# CorruptCore.net
KiCad netlist of a schematic drawn in EAGLE
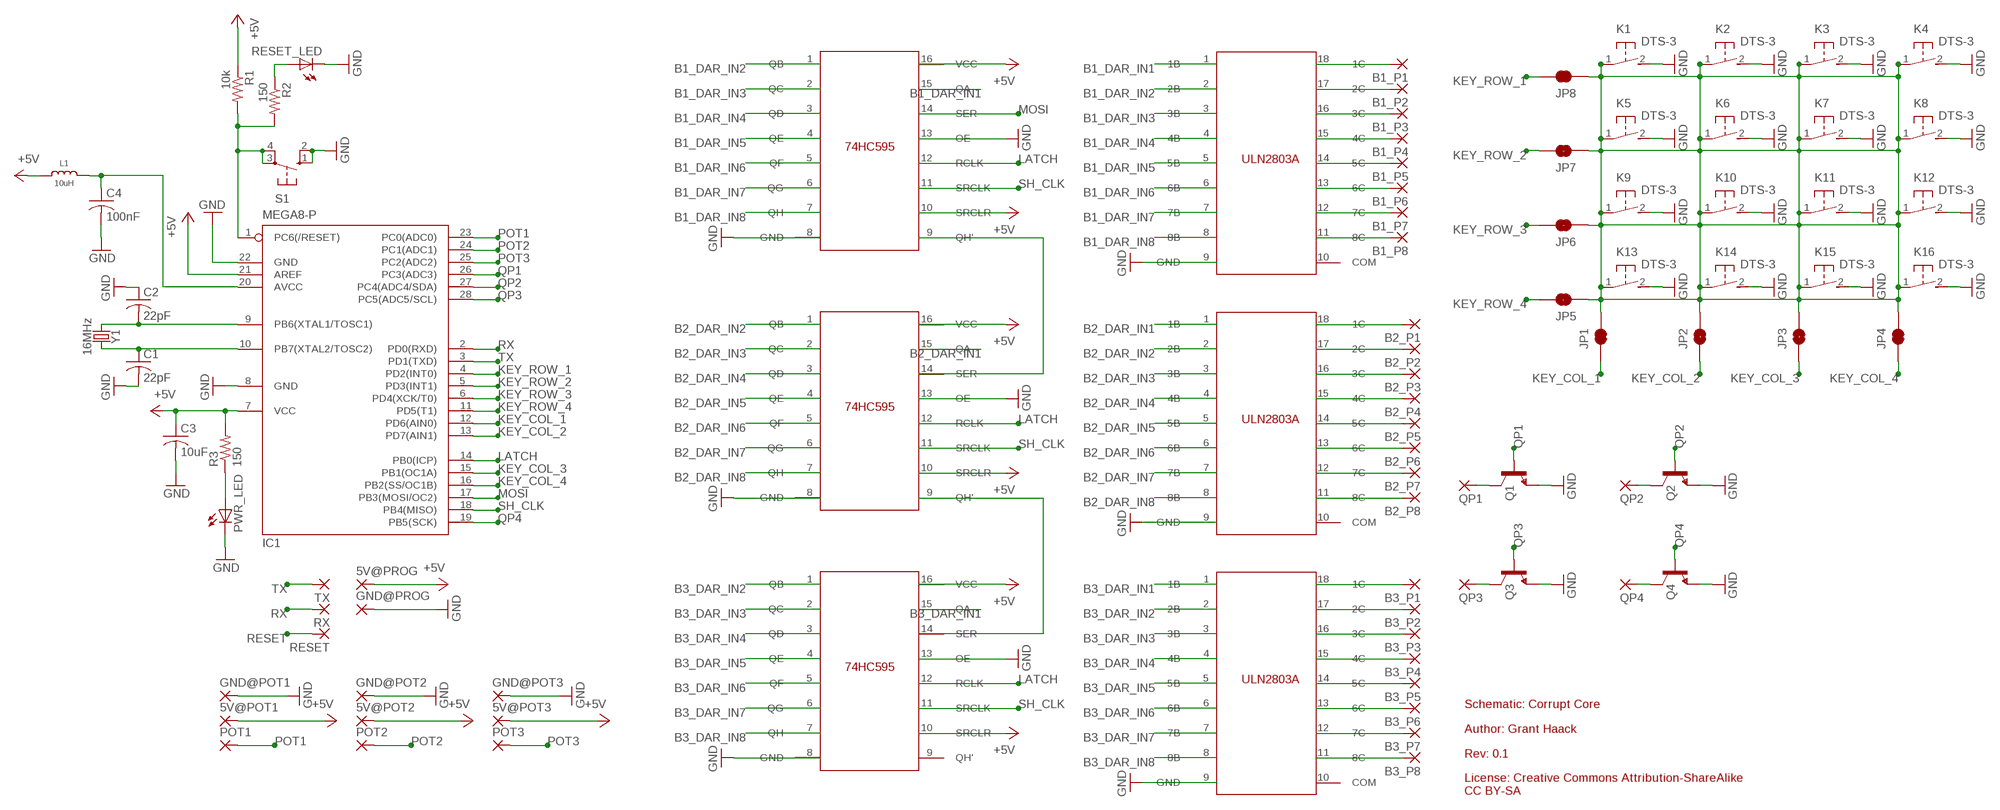
[diagram p0: schematic, sheet 1]

(export (version "E")
  (design (tool "Eeschema 10.0.6"))
  (components
    (comp (ref "5V@POT1")
      (value "2,54/1,1")
      (footprint "eagle-import:2,54_1,1")
      (libsource (lib "eagle-import") (part "2,54/1,1"))
    )
    (comp (ref "5V@POT2")
      (value "2,54/1,1")
      (footprint "eagle-import:2,54_1,1")
      (libsource (lib "eagle-import") (part "2,54/1,1"))
    )
    (comp (ref "5V@POT3")
      (value "2,54/1,1")
      (footprint "eagle-import:2,54_1,1")
      (libsource (lib "eagle-import") (part "2,54/1,1"))
    )
    (comp (ref "5V@PROG")
      (value "2,54/1,1")
      (footprint "eagle-import:2,54_1,1")
      (libsource (lib "eagle-import") (part "2,54/1,1"))
    )
    (comp (ref "B1_P1")
      (value "2,54/1,1")
      (footprint "eagle-import:2,54_1,1")
      (libsource (lib "eagle-import") (part "2,54/1,1"))
    )
    (comp (ref "B1_P2")
      (value "2,54/1,1")
      (footprint "eagle-import:2,54_1,1")
      (libsource (lib "eagle-import") (part "2,54/1,1"))
    )
    (comp (ref "B1_P3")
      (value "2,54/1,1")
      (footprint "eagle-import:2,54_1,1")
      (libsource (lib "eagle-import") (part "2,54/1,1"))
    )
    (comp (ref "B1_P4")
      (value "2,54/1,1")
      (footprint "eagle-import:2,54_1,1")
      (libsource (lib "eagle-import") (part "2,54/1,1"))
    )
    (comp (ref "B1_P5")
      (value "2,54/1,1")
      (footprint "eagle-import:2,54_1,1")
      (libsource (lib "eagle-import") (part "2,54/1,1"))
    )
    (comp (ref "B1_P6")
      (value "2,54/1,1")
      (footprint "eagle-import:2,54_1,1")
      (libsource (lib "eagle-import") (part "2,54/1,1"))
    )
    (comp (ref "B1_P7")
      (value "2,54/1,1")
      (footprint "eagle-import:2,54_1,1")
      (libsource (lib "eagle-import") (part "2,54/1,1"))
    )
    (comp (ref "B1_P8")
      (value "2,54/1,1")
      (footprint "eagle-import:2,54_1,1")
      (libsource (lib "eagle-import") (part "2,54/1,1"))
    )
    (comp (ref "B2_P1")
      (value "2,54/1,1")
      (footprint "eagle-import:2,54_1,1")
      (libsource (lib "eagle-import") (part "2,54/1,1"))
    )
    (comp (ref "B2_P2")
      (value "2,54/1,1")
      (footprint "eagle-import:2,54_1,1")
      (libsource (lib "eagle-import") (part "2,54/1,1"))
    )
    (comp (ref "B2_P3")
      (value "2,54/1,1")
      (footprint "eagle-import:2,54_1,1")
      (libsource (lib "eagle-import") (part "2,54/1,1"))
    )
    (comp (ref "B2_P4")
      (value "2,54/1,1")
      (footprint "eagle-import:2,54_1,1")
      (libsource (lib "eagle-import") (part "2,54/1,1"))
    )
    (comp (ref "B2_P5")
      (value "2,54/1,1")
      (footprint "eagle-import:2,54_1,1")
      (libsource (lib "eagle-import") (part "2,54/1,1"))
    )
    (comp (ref "B2_P6")
      (value "2,54/1,1")
      (footprint "eagle-import:2,54_1,1")
      (libsource (lib "eagle-import") (part "2,54/1,1"))
    )
    (comp (ref "B2_P7")
      (value "2,54/1,1")
      (footprint "eagle-import:2,54_1,1")
      (libsource (lib "eagle-import") (part "2,54/1,1"))
    )
    (comp (ref "B2_P8")
      (value "2,54/1,1")
      (footprint "eagle-import:2,54_1,1")
      (libsource (lib "eagle-import") (part "2,54/1,1"))
    )
    (comp (ref "B3_P1")
      (value "2,54/1,1")
      (footprint "eagle-import:2,54_1,1")
      (libsource (lib "eagle-import") (part "2,54/1,1"))
    )
    (comp (ref "B3_P2")
      (value "2,54/1,1")
      (footprint "eagle-import:2,54_1,1")
      (libsource (lib "eagle-import") (part "2,54/1,1"))
    )
    (comp (ref "B3_P3")
      (value "2,54/1,1")
      (footprint "eagle-import:2,54_1,1")
      (libsource (lib "eagle-import") (part "2,54/1,1"))
    )
    (comp (ref "B3_P4")
      (value "2,54/1,1")
      (footprint "eagle-import:2,54_1,1")
      (libsource (lib "eagle-import") (part "2,54/1,1"))
    )
    (comp (ref "B3_P5")
      (value "2,54/1,1")
      (footprint "eagle-import:2,54_1,1")
      (libsource (lib "eagle-import") (part "2,54/1,1"))
    )
    (comp (ref "B3_P6")
      (value "2,54/1,1")
      (footprint "eagle-import:2,54_1,1")
      (libsource (lib "eagle-import") (part "2,54/1,1"))
    )
    (comp (ref "B3_P7")
      (value "2,54/1,1")
      (footprint "eagle-import:2,54_1,1")
      (libsource (lib "eagle-import") (part "2,54/1,1"))
    )
    (comp (ref "B3_P8")
      (value "2,54/1,1")
      (footprint "eagle-import:2,54_1,1")
      (libsource (lib "eagle-import") (part "2,54/1,1"))
    )
    (comp (ref "C1")
      (value "22pF")
      (footprint "eagle-import:C0805")
      (libsource (lib "eagle-import") (part "C-USC0805"))
    )
    (comp (ref "C2")
      (value "22pF")
      (footprint "eagle-import:C0805")
      (libsource (lib "eagle-import") (part "C-USC0805"))
    )
    (comp (ref "C3")
      (value "10uF")
      (footprint "eagle-import:C0805")
      (libsource (lib "eagle-import") (part "C-USC0805"))
    )
    (comp (ref "C4")
      (value "100nF")
      (footprint "eagle-import:C0805")
      (libsource (lib "eagle-import") (part "C-USC0805"))
    )
    (comp (ref "GND@POT1")
      (value "2,54/1,1")
      (footprint "eagle-import:2,54_1,1")
      (libsource (lib "eagle-import") (part "2,54/1,1"))
    )
    (comp (ref "GND@POT2")
      (value "2,54/1,1")
      (footprint "eagle-import:2,54_1,1")
      (libsource (lib "eagle-import") (part "2,54/1,1"))
    )
    (comp (ref "GND@POT3")
      (value "2,54/1,1")
      (footprint "eagle-import:2,54_1,1")
      (libsource (lib "eagle-import") (part "2,54/1,1"))
    )
    (comp (ref "GND@PROG")
      (value "2,54/1,1")
      (footprint "eagle-import:2,54_1,1")
      (libsource (lib "eagle-import") (part "2,54/1,1"))
    )
    (comp (ref "IC1")
      (value "MEGA8-P")
      (footprint "eagle-import:DIL28-3")
      (libsource (lib "eagle-import") (part "MEGA8-P"))
    )
    (comp (ref "JP1")
      (value "JUMPER-SMT_2_NC_TRACE_NO-SILK")
      (footprint "eagle-import:SMT-JUMPER_2_NC_TRACE_NO-SILK")
      (libsource (lib "eagle-import") (part "JUMPER-SMT_2_NC_TRACE_NO-SILK"))
    )
    (comp (ref "JP2")
      (value "JUMPER-SMT_2_NC_TRACE_NO-SILK")
      (footprint "eagle-import:SMT-JUMPER_2_NC_TRACE_NO-SILK")
      (libsource (lib "eagle-import") (part "JUMPER-SMT_2_NC_TRACE_NO-SILK"))
    )
    (comp (ref "JP3")
      (value "JUMPER-SMT_2_NC_TRACE_NO-SILK")
      (footprint "eagle-import:SMT-JUMPER_2_NC_TRACE_NO-SILK")
      (libsource (lib "eagle-import") (part "JUMPER-SMT_2_NC_TRACE_NO-SILK"))
    )
    (comp (ref "JP4")
      (value "JUMPER-SMT_2_NC_TRACE_NO-SILK")
      (footprint "eagle-import:SMT-JUMPER_2_NC_TRACE_NO-SILK")
      (libsource (lib "eagle-import") (part "JUMPER-SMT_2_NC_TRACE_NO-SILK"))
    )
    (comp (ref "JP5")
      (value "JUMPER-SMT_2_NC_TRACE_NO-SILK")
      (footprint "eagle-import:SMT-JUMPER_2_NC_TRACE_NO-SILK")
      (libsource (lib "eagle-import") (part "JUMPER-SMT_2_NC_TRACE_NO-SILK"))
    )
    (comp (ref "JP6")
      (value "JUMPER-SMT_2_NC_TRACE_NO-SILK")
      (footprint "eagle-import:SMT-JUMPER_2_NC_TRACE_NO-SILK")
      (libsource (lib "eagle-import") (part "JUMPER-SMT_2_NC_TRACE_NO-SILK"))
    )
    (comp (ref "JP7")
      (value "JUMPER-SMT_2_NC_TRACE_NO-SILK")
      (footprint "eagle-import:SMT-JUMPER_2_NC_TRACE_NO-SILK")
      (libsource (lib "eagle-import") (part "JUMPER-SMT_2_NC_TRACE_NO-SILK"))
    )
    (comp (ref "JP8")
      (value "JUMPER-SMT_2_NC_TRACE_NO-SILK")
      (footprint "eagle-import:SMT-JUMPER_2_NC_TRACE_NO-SILK")
      (libsource (lib "eagle-import") (part "JUMPER-SMT_2_NC_TRACE_NO-SILK"))
    )
    (comp (ref "K1")
      (value "DTS-3")
      (footprint "eagle-import:DTS-3")
      (libsource (lib "eagle-import") (part "DTS-3"))
    )
    (comp (ref "K2")
      (value "DTS-3")
      (footprint "eagle-import:DTS-3")
      (libsource (lib "eagle-import") (part "DTS-3"))
    )
    (comp (ref "K3")
      (value "DTS-3")
      (footprint "eagle-import:DTS-3")
      (libsource (lib "eagle-import") (part "DTS-3"))
    )
    (comp (ref "K4")
      (value "DTS-3")
      (footprint "eagle-import:DTS-3")
      (libsource (lib "eagle-import") (part "DTS-3"))
    )
    (comp (ref "K5")
      (value "DTS-3")
      (footprint "eagle-import:DTS-3")
      (libsource (lib "eagle-import") (part "DTS-3"))
    )
    (comp (ref "K6")
      (value "DTS-3")
      (footprint "eagle-import:DTS-3")
      (libsource (lib "eagle-import") (part "DTS-3"))
    )
    (comp (ref "K7")
      (value "DTS-3")
      (footprint "eagle-import:DTS-3")
      (libsource (lib "eagle-import") (part "DTS-3"))
    )
    (comp (ref "K8")
      (value "DTS-3")
      (footprint "eagle-import:DTS-3")
      (libsource (lib "eagle-import") (part "DTS-3"))
    )
    (comp (ref "K9")
      (value "DTS-3")
      (footprint "eagle-import:DTS-3")
      (libsource (lib "eagle-import") (part "DTS-3"))
    )
    (comp (ref "K10")
      (value "DTS-3")
      (footprint "eagle-import:DTS-3")
      (libsource (lib "eagle-import") (part "DTS-3"))
    )
    (comp (ref "K11")
      (value "DTS-3")
      (footprint "eagle-import:DTS-3")
      (libsource (lib "eagle-import") (part "DTS-3"))
    )
    (comp (ref "K12")
      (value "DTS-3")
      (footprint "eagle-import:DTS-3")
      (libsource (lib "eagle-import") (part "DTS-3"))
    )
    (comp (ref "K13")
      (value "DTS-3")
      (footprint "eagle-import:DTS-3")
      (libsource (lib "eagle-import") (part "DTS-3"))
    )
    (comp (ref "K14")
      (value "DTS-3")
      (footprint "eagle-import:DTS-3")
      (libsource (lib "eagle-import") (part "DTS-3"))
    )
    (comp (ref "K15")
      (value "DTS-3")
      (footprint "eagle-import:DTS-3")
      (libsource (lib "eagle-import") (part "DTS-3"))
    )
    (comp (ref "K16")
      (value "DTS-3")
      (footprint "eagle-import:DTS-3")
      (libsource (lib "eagle-import") (part "DTS-3"))
    )
    (comp (ref "L1")
      (value "10uH")
      (footprint "eagle-import:MICROBUILDER__0805")
      (libsource (lib "eagle-import") (part "MICROBUILDER_INDUCTOR_0805"))
    )
    (comp (ref "POT1")
      (value "2,54/1,1")
      (footprint "eagle-import:2,54_1,1")
      (libsource (lib "eagle-import") (part "2,54/1,1"))
    )
    (comp (ref "POT2")
      (value "2,54/1,1")
      (footprint "eagle-import:2,54_1,1")
      (libsource (lib "eagle-import") (part "2,54/1,1"))
    )
    (comp (ref "POT3")
      (value "2,54/1,1")
      (footprint "eagle-import:2,54_1,1")
      (libsource (lib "eagle-import") (part "2,54/1,1"))
    )
    (comp (ref "PWR_LED")
      (value "LEDCHIPLED_0603")
      (footprint "eagle-import:CHIPLED_0603")
      (libsource (lib "eagle-import") (part "LEDCHIPLED_0603"))
    )
    (comp (ref "Q1")
      (value "TRANS_NPN-MMBTA42")
      (footprint "eagle-import:SOT23-3")
      (libsource (lib "eagle-import") (part "TRANS_NPN-MMBTA42"))
    )
    (comp (ref "Q2")
      (value "TRANS_NPN-MMBTA42")
      (footprint "eagle-import:SOT23-3")
      (libsource (lib "eagle-import") (part "TRANS_NPN-MMBTA42"))
    )
    (comp (ref "Q3")
      (value "TRANS_NPN-MMBTA42")
      (footprint "eagle-import:SOT23-3")
      (libsource (lib "eagle-import") (part "TRANS_NPN-MMBTA42"))
    )
    (comp (ref "Q4")
      (value "TRANS_NPN-MMBTA42")
      (footprint "eagle-import:SOT23-3")
      (libsource (lib "eagle-import") (part "TRANS_NPN-MMBTA42"))
    )
    (comp (ref "QP1")
      (value "2,54/1,1")
      (footprint "eagle-import:2,54_1,1")
      (libsource (lib "eagle-import") (part "2,54/1,1"))
    )
    (comp (ref "QP2")
      (value "2,54/1,1")
      (footprint "eagle-import:2,54_1,1")
      (libsource (lib "eagle-import") (part "2,54/1,1"))
    )
    (comp (ref "QP3")
      (value "2,54/1,1")
      (footprint "eagle-import:2,54_1,1")
      (libsource (lib "eagle-import") (part "2,54/1,1"))
    )
    (comp (ref "QP4")
      (value "2,54/1,1")
      (footprint "eagle-import:2,54_1,1")
      (libsource (lib "eagle-import") (part "2,54/1,1"))
    )
    (comp (ref "R1")
      (value "10k")
      (footprint "eagle-import:R0805")
      (libsource (lib "eagle-import") (part "R-US_R0805"))
    )
    (comp (ref "R2")
      (value "150")
      (footprint "eagle-import:R0805")
      (libsource (lib "eagle-import") (part "R-US_R0805"))
    )
    (comp (ref "R3")
      (value "150")
      (footprint "eagle-import:R0805")
      (libsource (lib "eagle-import") (part "R-US_R0805"))
    )
    (comp (ref "RESET")
      (value "2,54/1,1")
      (footprint "eagle-import:2,54_1,1")
      (libsource (lib "eagle-import") (part "2,54/1,1"))
    )
    (comp (ref "RESET_LED")
      (value "LEDCHIPLED_0603")
      (footprint "eagle-import:CHIPLED_0603")
      (libsource (lib "eagle-import") (part "LEDCHIPLED_0603"))
    )
    (comp (ref "RX")
      (value "2,54/1,1")
      (footprint "eagle-import:2,54_1,1")
      (libsource (lib "eagle-import") (part "2,54/1,1"))
    )
    (comp (ref "S1")
      (value "10-XX")
      (footprint "eagle-import:B3F-10XX")
      (fields (field (name "MPN") "B3F-1000"))
      (libsource (lib "eagle-import") (part "10-XX"))
    )
    (comp (ref "TX")
      (value "2,54/1,1")
      (footprint "eagle-import:2,54_1,1")
      (libsource (lib "eagle-import") (part "2,54/1,1"))
    )
    (comp (ref "U$1")
      (value "SN74HC595N")
      (footprint "eagle-import:DIL16")
      (libsource (lib "eagle-import") (part "SN74HC595N"))
    )
    (comp (ref "U$2")
      (value "ULN2803A")
      (footprint "eagle-import:DIL18")
      (libsource (lib "eagle-import") (part "ULN2803A"))
    )
    (comp (ref "U$3")
      (value "SN74HC595N")
      (footprint "eagle-import:DIL16")
      (libsource (lib "eagle-import") (part "SN74HC595N"))
    )
    (comp (ref "U$4")
      (value "ULN2803A")
      (footprint "eagle-import:DIL18")
      (libsource (lib "eagle-import") (part "ULN2803A"))
    )
    (comp (ref "U$5")
      (value "SN74HC595N")
      (footprint "eagle-import:DIL16")
      (libsource (lib "eagle-import") (part "SN74HC595N"))
    )
    (comp (ref "U$6")
      (value "ULN2803A")
      (footprint "eagle-import:DIL18")
      (libsource (lib "eagle-import") (part "ULN2803A"))
    )
    (comp (ref "Y1")
      (value "16MHz")
      (footprint "eagle-import:HC49US")
      (libsource (lib "eagle-import") (part "CRYSTAL-16MHZPTH-HC49US"))
    )
  )
  (nets
    (net (code "1") (name "+5V") (class "Default")
      (node (ref "5V@POT1") (pin "1") (pinfunction "P_1") (pintype "passive"))
      (node (ref "5V@POT2") (pin "1") (pinfunction "P_1") (pintype "passive"))
      (node (ref "5V@POT3") (pin "1") (pinfunction "P_1") (pintype "passive"))
      (node (ref "5V@PROG") (pin "1") (pinfunction "P_1") (pintype "passive"))
      (node (ref "C3") (pin "1") (pinfunction "1_1") (pintype "passive"))
      (node (ref "IC1") (pin "21") (pinfunction "AREF_21") (pintype "passive"))
      (node (ref "IC1") (pin "7") (pinfunction "VCC_7") (pintype "power_in"))
      (node (ref "L1") (pin "1") (pinfunction "1_1") (pintype "passive"))
      (node (ref "R1") (pin "1") (pinfunction "1_1") (pintype "passive"))
      (node (ref "R3") (pin "2") (pinfunction "2_2") (pintype "passive"))
      (node (ref "U$1") (pin "10") (pinfunction "SRCLR_10") (pintype "bidirectional"))
      (node (ref "U$1") (pin "16") (pinfunction "VCC_16") (pintype "bidirectional"))
      (node (ref "U$3") (pin "10") (pinfunction "SRCLR_10") (pintype "bidirectional"))
      (node (ref "U$3") (pin "16") (pinfunction "VCC_16") (pintype "bidirectional"))
      (node (ref "U$5") (pin "10") (pinfunction "SRCLR_10") (pintype "bidirectional"))
      (node (ref "U$5") (pin "16") (pinfunction "VCC_16") (pintype "bidirectional"))
    )
    (net (code "2") (name "/B1_DAR_IN1") (class "Default")
      (node (ref "U$1") (pin "15") (pinfunction "QA_15") (pintype "bidirectional"))
      (node (ref "U$2") (pin "1") (pinfunction "1B_1") (pintype "bidirectional"))
    )
    (net (code "3") (name "/B1_DAR_IN2") (class "Default")
      (node (ref "U$1") (pin "1") (pinfunction "QB_1") (pintype "bidirectional"))
      (node (ref "U$2") (pin "2") (pinfunction "2B_2") (pintype "bidirectional"))
    )
    (net (code "4") (name "/B1_DAR_IN3") (class "Default")
      (node (ref "U$1") (pin "2") (pinfunction "QC_2") (pintype "bidirectional"))
      (node (ref "U$2") (pin "3") (pinfunction "3B_3") (pintype "bidirectional"))
    )
    (net (code "5") (name "/B1_DAR_IN4") (class "Default")
      (node (ref "U$1") (pin "3") (pinfunction "QD_3") (pintype "bidirectional"))
      (node (ref "U$2") (pin "4") (pinfunction "4B_4") (pintype "bidirectional"))
    )
    (net (code "6") (name "/B1_DAR_IN5") (class "Default")
      (node (ref "U$1") (pin "4") (pinfunction "QE_4") (pintype "bidirectional"))
      (node (ref "U$2") (pin "5") (pinfunction "5B_5") (pintype "bidirectional"))
    )
    (net (code "7") (name "/B1_DAR_IN6") (class "Default")
      (node (ref "U$1") (pin "5") (pinfunction "QF_5") (pintype "bidirectional"))
      (node (ref "U$2") (pin "6") (pinfunction "6B_6") (pintype "bidirectional"))
    )
    (net (code "8") (name "/B1_DAR_IN7") (class "Default")
      (node (ref "U$1") (pin "6") (pinfunction "QG_6") (pintype "bidirectional"))
      (node (ref "U$2") (pin "7") (pinfunction "7B_7") (pintype "bidirectional"))
    )
    (net (code "9") (name "/B1_DAR_IN8") (class "Default")
      (node (ref "U$1") (pin "7") (pinfunction "QH_7") (pintype "bidirectional"))
      (node (ref "U$2") (pin "8") (pinfunction "8B_8") (pintype "bidirectional"))
    )
    (net (code "10") (name "/B2_DAR_IN1") (class "Default")
      (node (ref "U$3") (pin "15") (pinfunction "QA_15") (pintype "bidirectional"))
      (node (ref "U$4") (pin "1") (pinfunction "1B_1") (pintype "bidirectional"))
    )
    (net (code "11") (name "/B2_DAR_IN2") (class "Default")
      (node (ref "U$3") (pin "1") (pinfunction "QB_1") (pintype "bidirectional"))
      (node (ref "U$4") (pin "2") (pinfunction "2B_2") (pintype "bidirectional"))
    )
    (net (code "12") (name "/B2_DAR_IN3") (class "Default")
      (node (ref "U$3") (pin "2") (pinfunction "QC_2") (pintype "bidirectional"))
      (node (ref "U$4") (pin "3") (pinfunction "3B_3") (pintype "bidirectional"))
    )
    (net (code "13") (name "/B2_DAR_IN4") (class "Default")
      (node (ref "U$3") (pin "3") (pinfunction "QD_3") (pintype "bidirectional"))
      (node (ref "U$4") (pin "4") (pinfunction "4B_4") (pintype "bidirectional"))
    )
    (net (code "14") (name "/B2_DAR_IN5") (class "Default")
      (node (ref "U$3") (pin "4") (pinfunction "QE_4") (pintype "bidirectional"))
      (node (ref "U$4") (pin "5") (pinfunction "5B_5") (pintype "bidirectional"))
    )
    (net (code "15") (name "/B2_DAR_IN6") (class "Default")
      (node (ref "U$3") (pin "5") (pinfunction "QF_5") (pintype "bidirectional"))
      (node (ref "U$4") (pin "6") (pinfunction "6B_6") (pintype "bidirectional"))
    )
    (net (code "16") (name "/B2_DAR_IN7") (class "Default")
      (node (ref "U$3") (pin "6") (pinfunction "QG_6") (pintype "bidirectional"))
      (node (ref "U$4") (pin "7") (pinfunction "7B_7") (pintype "bidirectional"))
    )
    (net (code "17") (name "/B2_DAR_IN8") (class "Default")
      (node (ref "U$3") (pin "7") (pinfunction "QH_7") (pintype "bidirectional"))
      (node (ref "U$4") (pin "8") (pinfunction "8B_8") (pintype "bidirectional"))
    )
    (net (code "18") (name "/B3_DAR_IN1") (class "Default")
      (node (ref "U$5") (pin "15") (pinfunction "QA_15") (pintype "bidirectional"))
      (node (ref "U$6") (pin "1") (pinfunction "1B_1") (pintype "bidirectional"))
    )
    (net (code "19") (name "/B3_DAR_IN2") (class "Default")
      (node (ref "U$5") (pin "1") (pinfunction "QB_1") (pintype "bidirectional"))
      (node (ref "U$6") (pin "2") (pinfunction "2B_2") (pintype "bidirectional"))
    )
    (net (code "20") (name "/B3_DAR_IN3") (class "Default")
      (node (ref "U$5") (pin "2") (pinfunction "QC_2") (pintype "bidirectional"))
      (node (ref "U$6") (pin "3") (pinfunction "3B_3") (pintype "bidirectional"))
    )
    (net (code "21") (name "/B3_DAR_IN4") (class "Default")
      (node (ref "U$5") (pin "3") (pinfunction "QD_3") (pintype "bidirectional"))
      (node (ref "U$6") (pin "4") (pinfunction "4B_4") (pintype "bidirectional"))
    )
    (net (code "22") (name "/B3_DAR_IN5") (class "Default")
      (node (ref "U$5") (pin "4") (pinfunction "QE_4") (pintype "bidirectional"))
      (node (ref "U$6") (pin "5") (pinfunction "5B_5") (pintype "bidirectional"))
    )
    (net (code "23") (name "/B3_DAR_IN6") (class "Default")
      (node (ref "U$5") (pin "5") (pinfunction "QF_5") (pintype "bidirectional"))
      (node (ref "U$6") (pin "6") (pinfunction "6B_6") (pintype "bidirectional"))
    )
    (net (code "24") (name "/B3_DAR_IN7") (class "Default")
      (node (ref "U$5") (pin "6") (pinfunction "QG_6") (pintype "bidirectional"))
      (node (ref "U$6") (pin "7") (pinfunction "7B_7") (pintype "bidirectional"))
    )
    (net (code "25") (name "/B3_DAR_IN8") (class "Default")
      (node (ref "U$5") (pin "7") (pinfunction "QH_7") (pintype "bidirectional"))
      (node (ref "U$6") (pin "8") (pinfunction "8B_8") (pintype "bidirectional"))
    )
    (net (code "26") (name "/KEY_COL_1") (class "Default")
      (node (ref "IC1") (pin "12") (pinfunction "PD6(AIN0)_12") (pintype "bidirectional"))
      (node (ref "JP1") (pin "1") (pinfunction "1_1") (pintype "passive"))
    )
    (net (code "27") (name "/KEY_COL_2") (class "Default")
      (node (ref "IC1") (pin "13") (pinfunction "PD7(AIN1)_13") (pintype "bidirectional"))
      (node (ref "JP2") (pin "1") (pinfunction "1_1") (pintype "passive"))
    )
    (net (code "28") (name "/KEY_COL_3") (class "Default")
      (node (ref "IC1") (pin "15") (pinfunction "PB1(OC1A)_15") (pintype "bidirectional"))
      (node (ref "JP3") (pin "1") (pinfunction "1_1") (pintype "passive"))
    )
    (net (code "29") (name "/KEY_COL_4") (class "Default")
      (node (ref "IC1") (pin "16") (pinfunction "PB2(SS/OC1B)_16") (pintype "bidirectional"))
      (node (ref "JP4") (pin "1") (pinfunction "1_1") (pintype "passive"))
    )
    (net (code "30") (name "/KEY_ROW_1") (class "Default")
      (node (ref "IC1") (pin "4") (pinfunction "PD2(INT0)_4") (pintype "bidirectional"))
      (node (ref "JP8") (pin "2") (pinfunction "2_2") (pintype "passive"))
    )
    (net (code "31") (name "/KEY_ROW_2") (class "Default")
      (node (ref "IC1") (pin "5") (pinfunction "PD3(INT1)_5") (pintype "bidirectional"))
      (node (ref "JP7") (pin "2") (pinfunction "2_2") (pintype "passive"))
    )
    (net (code "32") (name "/KEY_ROW_3") (class "Default")
      (node (ref "IC1") (pin "6") (pinfunction "PD4(XCK/T0)_6") (pintype "bidirectional"))
      (node (ref "JP6") (pin "2") (pinfunction "2_2") (pintype "passive"))
    )
    (net (code "33") (name "/KEY_ROW_4") (class "Default")
      (node (ref "IC1") (pin "11") (pinfunction "PD5(T1)_11") (pintype "bidirectional"))
      (node (ref "JP5") (pin "2") (pinfunction "2_2") (pintype "passive"))
    )
    (net (code "34") (name "/LATCH") (class "Default")
      (node (ref "IC1") (pin "14") (pinfunction "PB0(ICP)_14") (pintype "bidirectional"))
      (node (ref "U$1") (pin "12") (pinfunction "RCLK_12") (pintype "bidirectional"))
      (node (ref "U$3") (pin "12") (pinfunction "RCLK_12") (pintype "bidirectional"))
      (node (ref "U$5") (pin "12") (pinfunction "RCLK_12") (pintype "bidirectional"))
    )
    (net (code "35") (name "/MOSI") (class "Default")
      (node (ref "IC1") (pin "17") (pinfunction "PB3(MOSI/OC2)_17") (pintype "bidirectional"))
      (node (ref "U$1") (pin "14") (pinfunction "SER_14") (pintype "bidirectional"))
    )
    (net (code "36") (name "/POT1") (class "Default")
      (node (ref "IC1") (pin "23") (pinfunction "PC0(ADC0)_23") (pintype "bidirectional"))
      (node (ref "POT1") (pin "1") (pinfunction "P_1") (pintype "passive"))
    )
    (net (code "37") (name "/POT2") (class "Default")
      (node (ref "IC1") (pin "24") (pinfunction "PC1(ADC1)_24") (pintype "bidirectional"))
      (node (ref "POT2") (pin "1") (pinfunction "P_1") (pintype "passive"))
    )
    (net (code "38") (name "/POT3") (class "Default")
      (node (ref "IC1") (pin "25") (pinfunction "PC2(ADC2)_25") (pintype "bidirectional"))
      (node (ref "POT3") (pin "1") (pinfunction "P_1") (pintype "passive"))
    )
    (net (code "39") (name "/QP1") (class "Default")
      (node (ref "IC1") (pin "26") (pinfunction "PC3(ADC3)_26") (pintype "bidirectional"))
      (node (ref "Q1") (pin "1") (pinfunction "B_1") (pintype "passive"))
    )
    (net (code "40") (name "/QP2") (class "Default")
      (node (ref "IC1") (pin "27") (pinfunction "PC4(ADC4/SDA)_27") (pintype "bidirectional"))
      (node (ref "Q2") (pin "1") (pinfunction "B_1") (pintype "passive"))
    )
    (net (code "41") (name "/QP3") (class "Default")
      (node (ref "IC1") (pin "28") (pinfunction "PC5(ADC5/SCL)_28") (pintype "bidirectional"))
      (node (ref "Q3") (pin "1") (pinfunction "B_1") (pintype "passive"))
    )
    (net (code "42") (name "/QP4") (class "Default")
      (node (ref "IC1") (pin "19") (pinfunction "PB5(SCK)_19") (pintype "bidirectional"))
      (node (ref "Q4") (pin "1") (pinfunction "B_1") (pintype "passive"))
    )
    (net (code "43") (name "/RESET") (class "Default")
      (node (ref "IC1") (pin "1") (pinfunction "PC6(/RESET)_1") (pintype "bidirectional"))
      (node (ref "R1") (pin "2") (pinfunction "2_2") (pintype "passive"))
      (node (ref "R2") (pin "2") (pinfunction "2_2") (pintype "passive"))
      (node (ref "RESET") (pin "1") (pinfunction "P_1") (pintype "passive"))
      (node (ref "S1") (pin "3") (pinfunction "P_3") (pintype "passive"))
      (node (ref "S1") (pin "4") (pinfunction "P1_4") (pintype "passive"))
    )
    (net (code "44") (name "/RX") (class "Default")
      (node (ref "IC1") (pin "2") (pinfunction "PD0(RXD)_2") (pintype "bidirectional"))
      (node (ref "RX") (pin "1") (pinfunction "P_1") (pintype "passive"))
    )
    (net (code "45") (name "/SH_CLK") (class "Default")
      (node (ref "IC1") (pin "18") (pinfunction "PB4(MISO)_18") (pintype "bidirectional"))
      (node (ref "U$1") (pin "11") (pinfunction "SRCLK_11") (pintype "bidirectional"))
      (node (ref "U$3") (pin "11") (pinfunction "SRCLK_11") (pintype "bidirectional"))
      (node (ref "U$5") (pin "11") (pinfunction "SRCLK_11") (pintype "bidirectional"))
    )
    (net (code "46") (name "/TX") (class "Default")
      (node (ref "IC1") (pin "3") (pinfunction "PD1(TXD)_3") (pintype "bidirectional"))
      (node (ref "TX") (pin "1") (pinfunction "P_1") (pintype "passive"))
    )
    (net (code "47") (name "GND") (class "Default")
      (node (ref "C1") (pin "2") (pinfunction "2_2") (pintype "passive"))
      (node (ref "C2") (pin "1") (pinfunction "1_1") (pintype "passive"))
      (node (ref "C3") (pin "2") (pinfunction "2_2") (pintype "passive"))
      (node (ref "C4") (pin "2") (pinfunction "2_2") (pintype "passive"))
      (node (ref "GND@POT1") (pin "1") (pinfunction "P_1") (pintype "passive"))
      (node (ref "GND@POT2") (pin "1") (pinfunction "P_1") (pintype "passive"))
      (node (ref "GND@POT3") (pin "1") (pinfunction "P_1") (pintype "passive"))
      (node (ref "GND@PROG") (pin "1") (pinfunction "P_1") (pintype "passive"))
      (node (ref "IC1") (pin "22") (pinfunction "GND_22") (pintype "power_in"))
      (node (ref "IC1") (pin "8") (pinfunction "GND_8") (pintype "power_in"))
      (node (ref "K1") (pin "2") (pinfunction "2_2") (pintype "passive"))
      (node (ref "K10") (pin "2") (pinfunction "2_2") (pintype "passive"))
      (node (ref "K11") (pin "2") (pinfunction "2_2") (pintype "passive"))
      (node (ref "K12") (pin "2") (pinfunction "2_2") (pintype "passive"))
      (node (ref "K13") (pin "2") (pinfunction "2_2") (pintype "passive"))
      (node (ref "K14") (pin "2") (pinfunction "2_2") (pintype "passive"))
      (node (ref "K15") (pin "2") (pinfunction "2_2") (pintype "passive"))
      (node (ref "K16") (pin "2") (pinfunction "2_2") (pintype "passive"))
      (node (ref "K2") (pin "2") (pinfunction "2_2") (pintype "passive"))
      (node (ref "K3") (pin "2") (pinfunction "2_2") (pintype "passive"))
      (node (ref "K4") (pin "2") (pinfunction "2_2") (pintype "passive"))
      (node (ref "K5") (pin "2") (pinfunction "2_2") (pintype "passive"))
      (node (ref "K6") (pin "2") (pinfunction "2_2") (pintype "passive"))
      (node (ref "K7") (pin "2") (pinfunction "2_2") (pintype "passive"))
      (node (ref "K8") (pin "2") (pinfunction "2_2") (pintype "passive"))
      (node (ref "K9") (pin "2") (pinfunction "2_2") (pintype "passive"))
      (node (ref "PWR_LED") (pin "C") (pinfunction "C_C") (pintype "passive"))
      (node (ref "Q1") (pin "2") (pinfunction "E_2") (pintype "passive"))
      (node (ref "Q2") (pin "2") (pinfunction "E_2") (pintype "passive"))
      (node (ref "Q3") (pin "2") (pinfunction "E_2") (pintype "passive"))
      (node (ref "Q4") (pin "2") (pinfunction "E_2") (pintype "passive"))
      (node (ref "RESET_LED") (pin "C") (pinfunction "C_C") (pintype "passive"))
      (node (ref "S1") (pin "1") (pinfunction "S_1") (pintype "passive"))
      (node (ref "S1") (pin "2") (pinfunction "S1_2") (pintype "passive"))
      (node (ref "U$1") (pin "13") (pinfunction "OE_13") (pintype "bidirectional"))
      (node (ref "U$1") (pin "8") (pinfunction "GND_8") (pintype "bidirectional"))
      (node (ref "U$2") (pin "9") (pinfunction "GND_9") (pintype "bidirectional"))
      (node (ref "U$3") (pin "13") (pinfunction "OE_13") (pintype "bidirectional"))
      (node (ref "U$3") (pin "8") (pinfunction "GND_8") (pintype "bidirectional"))
      (node (ref "U$4") (pin "9") (pinfunction "GND_9") (pintype "bidirectional"))
      (node (ref "U$5") (pin "13") (pinfunction "OE_13") (pintype "bidirectional"))
      (node (ref "U$5") (pin "8") (pinfunction "GND_8") (pintype "bidirectional"))
      (node (ref "U$6") (pin "9") (pinfunction "GND_9") (pintype "bidirectional"))
    )
    (net (code "48") (name "Net-(B1_P1-P)") (class "Default")
      (node (ref "B1_P1") (pin "1") (pinfunction "P_1") (pintype "passive"))
      (node (ref "U$2") (pin "18") (pinfunction "1C_18") (pintype "bidirectional"))
    )
    (net (code "49") (name "Net-(B1_P2-P)") (class "Default")
      (node (ref "B1_P2") (pin "1") (pinfunction "P_1") (pintype "passive"))
      (node (ref "U$2") (pin "17") (pinfunction "2C_17") (pintype "bidirectional"))
    )
    (net (code "50") (name "Net-(B1_P3-P)") (class "Default")
      (node (ref "B1_P3") (pin "1") (pinfunction "P_1") (pintype "passive"))
      (node (ref "U$2") (pin "16") (pinfunction "3C_16") (pintype "bidirectional"))
    )
    (net (code "51") (name "Net-(B1_P4-P)") (class "Default")
      (node (ref "B1_P4") (pin "1") (pinfunction "P_1") (pintype "passive"))
      (node (ref "U$2") (pin "15") (pinfunction "4C_15") (pintype "bidirectional"))
    )
    (net (code "52") (name "Net-(B1_P5-P)") (class "Default")
      (node (ref "B1_P5") (pin "1") (pinfunction "P_1") (pintype "passive"))
      (node (ref "U$2") (pin "14") (pinfunction "5C_14") (pintype "bidirectional"))
    )
    (net (code "53") (name "Net-(B1_P6-P)") (class "Default")
      (node (ref "B1_P6") (pin "1") (pinfunction "P_1") (pintype "passive"))
      (node (ref "U$2") (pin "13") (pinfunction "6C_13") (pintype "bidirectional"))
    )
    (net (code "54") (name "Net-(B1_P7-P)") (class "Default")
      (node (ref "B1_P7") (pin "1") (pinfunction "P_1") (pintype "passive"))
      (node (ref "U$2") (pin "12") (pinfunction "7C_12") (pintype "bidirectional"))
    )
    (net (code "55") (name "Net-(B1_P8-P)") (class "Default")
      (node (ref "B1_P8") (pin "1") (pinfunction "P_1") (pintype "passive"))
      (node (ref "U$2") (pin "11") (pinfunction "8C_11") (pintype "bidirectional"))
    )
    (net (code "56") (name "Net-(B2_P1-P)") (class "Default")
      (node (ref "B2_P1") (pin "1") (pinfunction "P_1") (pintype "passive"))
      (node (ref "U$4") (pin "18") (pinfunction "1C_18") (pintype "bidirectional"))
    )
    (net (code "57") (name "Net-(B2_P2-P)") (class "Default")
      (node (ref "B2_P2") (pin "1") (pinfunction "P_1") (pintype "passive"))
      (node (ref "U$4") (pin "17") (pinfunction "2C_17") (pintype "bidirectional"))
    )
    (net (code "58") (name "Net-(B2_P3-P)") (class "Default")
      (node (ref "B2_P3") (pin "1") (pinfunction "P_1") (pintype "passive"))
      (node (ref "U$4") (pin "16") (pinfunction "3C_16") (pintype "bidirectional"))
    )
    (net (code "59") (name "Net-(B2_P4-P)") (class "Default")
      (node (ref "B2_P4") (pin "1") (pinfunction "P_1") (pintype "passive"))
      (node (ref "U$4") (pin "15") (pinfunction "4C_15") (pintype "bidirectional"))
    )
    (net (code "60") (name "Net-(B2_P5-P)") (class "Default")
      (node (ref "B2_P5") (pin "1") (pinfunction "P_1") (pintype "passive"))
      (node (ref "U$4") (pin "14") (pinfunction "5C_14") (pintype "bidirectional"))
    )
    (net (code "61") (name "Net-(B2_P6-P)") (class "Default")
      (node (ref "B2_P6") (pin "1") (pinfunction "P_1") (pintype "passive"))
      (node (ref "U$4") (pin "13") (pinfunction "6C_13") (pintype "bidirectional"))
    )
    (net (code "62") (name "Net-(B2_P7-P)") (class "Default")
      (node (ref "B2_P7") (pin "1") (pinfunction "P_1") (pintype "passive"))
      (node (ref "U$4") (pin "12") (pinfunction "7C_12") (pintype "bidirectional"))
    )
    (net (code "63") (name "Net-(B2_P8-P)") (class "Default")
      (node (ref "B2_P8") (pin "1") (pinfunction "P_1") (pintype "passive"))
      (node (ref "U$4") (pin "11") (pinfunction "8C_11") (pintype "bidirectional"))
    )
    (net (code "64") (name "Net-(B3_P1-P)") (class "Default")
      (node (ref "B3_P1") (pin "1") (pinfunction "P_1") (pintype "passive"))
      (node (ref "U$6") (pin "18") (pinfunction "1C_18") (pintype "bidirectional"))
    )
    (net (code "65") (name "Net-(B3_P2-P)") (class "Default")
      (node (ref "B3_P2") (pin "1") (pinfunction "P_1") (pintype "passive"))
      (node (ref "U$6") (pin "17") (pinfunction "2C_17") (pintype "bidirectional"))
    )
    (net (code "66") (name "Net-(B3_P3-P)") (class "Default")
      (node (ref "B3_P3") (pin "1") (pinfunction "P_1") (pintype "passive"))
      (node (ref "U$6") (pin "16") (pinfunction "3C_16") (pintype "bidirectional"))
    )
    (net (code "67") (name "Net-(B3_P4-P)") (class "Default")
      (node (ref "B3_P4") (pin "1") (pinfunction "P_1") (pintype "passive"))
      (node (ref "U$6") (pin "15") (pinfunction "4C_15") (pintype "bidirectional"))
    )
    (net (code "68") (name "Net-(B3_P5-P)") (class "Default")
      (node (ref "B3_P5") (pin "1") (pinfunction "P_1") (pintype "passive"))
      (node (ref "U$6") (pin "14") (pinfunction "5C_14") (pintype "bidirectional"))
    )
    (net (code "69") (name "Net-(B3_P6-P)") (class "Default")
      (node (ref "B3_P6") (pin "1") (pinfunction "P_1") (pintype "passive"))
      (node (ref "U$6") (pin "13") (pinfunction "6C_13") (pintype "bidirectional"))
    )
    (net (code "70") (name "Net-(B3_P7-P)") (class "Default")
      (node (ref "B3_P7") (pin "1") (pinfunction "P_1") (pintype "passive"))
      (node (ref "U$6") (pin "12") (pinfunction "7C_12") (pintype "bidirectional"))
    )
    (net (code "71") (name "Net-(B3_P8-P)") (class "Default")
      (node (ref "B3_P8") (pin "1") (pinfunction "P_1") (pintype "passive"))
      (node (ref "U$6") (pin "11") (pinfunction "8C_11") (pintype "bidirectional"))
    )
    (net (code "72") (name "Net-(IC1-AVCC)") (class "Default")
      (node (ref "C4") (pin "1") (pinfunction "1_1") (pintype "passive"))
      (node (ref "IC1") (pin "20") (pinfunction "AVCC_20") (pintype "power_in"))
      (node (ref "L1") (pin "2") (pinfunction "2_2") (pintype "passive"))
    )
    (net (code "73") (name "Net-(IC1-PB6(XTAL1{slash}TOSC1))") (class "Default")
      (node (ref "C2") (pin "2") (pinfunction "2_2") (pintype "passive"))
      (node (ref "IC1") (pin "9") (pinfunction "PB6(XTAL1/TOSC1)_9") (pintype "bidirectional"))
      (node (ref "Y1") (pin "1") (pinfunction "1_1") (pintype "passive"))
    )
    (net (code "74") (name "Net-(IC1-PB7(XTAL2{slash}TOSC2))") (class "Default")
      (node (ref "C1") (pin "1") (pinfunction "1_1") (pintype "passive"))
      (node (ref "IC1") (pin "10") (pinfunction "PB7(XTAL2/TOSC2)_10") (pintype "bidirectional"))
      (node (ref "Y1") (pin "2") (pinfunction "2_2") (pintype "passive"))
    )
    (net (code "75") (name "Net-(JP1-Pad2)") (class "Default")
      (node (ref "JP1") (pin "2") (pinfunction "2_2") (pintype "passive"))
      (node (ref "JP2") (pin "2") (pinfunction "2_2") (pintype "passive"))
      (node (ref "JP3") (pin "2") (pinfunction "2_2") (pintype "passive"))
      (node (ref "JP4") (pin "2") (pinfunction "2_2") (pintype "passive"))
      (node (ref "JP5") (pin "1") (pinfunction "1_1") (pintype "passive"))
      (node (ref "JP6") (pin "1") (pinfunction "1_1") (pintype "passive"))
      (node (ref "JP7") (pin "1") (pinfunction "1_1") (pintype "passive"))
      (node (ref "JP8") (pin "1") (pinfunction "1_1") (pintype "passive"))
      (node (ref "K1") (pin "1") (pinfunction "1_1") (pintype "passive"))
      (node (ref "K10") (pin "1") (pinfunction "1_1") (pintype "passive"))
      (node (ref "K11") (pin "1") (pinfunction "1_1") (pintype "passive"))
      (node (ref "K12") (pin "1") (pinfunction "1_1") (pintype "passive"))
      (node (ref "K13") (pin "1") (pinfunction "1_1") (pintype "passive"))
      (node (ref "K14") (pin "1") (pinfunction "1_1") (pintype "passive"))
      (node (ref "K15") (pin "1") (pinfunction "1_1") (pintype "passive"))
      (node (ref "K16") (pin "1") (pinfunction "1_1") (pintype "passive"))
      (node (ref "K2") (pin "1") (pinfunction "1_1") (pintype "passive"))
      (node (ref "K3") (pin "1") (pinfunction "1_1") (pintype "passive"))
      (node (ref "K4") (pin "1") (pinfunction "1_1") (pintype "passive"))
      (node (ref "K5") (pin "1") (pinfunction "1_1") (pintype "passive"))
      (node (ref "K6") (pin "1") (pinfunction "1_1") (pintype "passive"))
      (node (ref "K7") (pin "1") (pinfunction "1_1") (pintype "passive"))
      (node (ref "K8") (pin "1") (pinfunction "1_1") (pintype "passive"))
      (node (ref "K9") (pin "1") (pinfunction "1_1") (pintype "passive"))
    )
    (net (code "76") (name "Net-(PWR_LED-PadA)") (class "Default")
      (node (ref "PWR_LED") (pin "A") (pinfunction "A_A") (pintype "passive"))
      (node (ref "R3") (pin "1") (pinfunction "1_1") (pintype "passive"))
    )
    (net (code "77") (name "Net-(Q1-C)") (class "Default")
      (node (ref "Q1") (pin "3") (pinfunction "C_3") (pintype "passive"))
      (node (ref "QP1") (pin "1") (pinfunction "P_1") (pintype "passive"))
    )
    (net (code "78") (name "Net-(Q2-C)") (class "Default")
      (node (ref "Q2") (pin "3") (pinfunction "C_3") (pintype "passive"))
      (node (ref "QP2") (pin "1") (pinfunction "P_1") (pintype "passive"))
    )
    (net (code "79") (name "Net-(Q3-C)") (class "Default")
      (node (ref "Q3") (pin "3") (pinfunction "C_3") (pintype "passive"))
      (node (ref "QP3") (pin "1") (pinfunction "P_1") (pintype "passive"))
    )
    (net (code "80") (name "Net-(Q4-C)") (class "Default")
      (node (ref "Q4") (pin "3") (pinfunction "C_3") (pintype "passive"))
      (node (ref "QP4") (pin "1") (pinfunction "P_1") (pintype "passive"))
    )
    (net (code "81") (name "Net-(R2-Pad1)") (class "Default")
      (node (ref "R2") (pin "1") (pinfunction "1_1") (pintype "passive"))
      (node (ref "RESET_LED") (pin "A") (pinfunction "A_A") (pintype "passive"))
    )
    (net (code "82") (name "Net-(U$1-QH')") (class "Default")
      (node (ref "U$1") (pin "9") (pinfunction "QH'_9") (pintype "bidirectional"))
      (node (ref "U$3") (pin "14") (pinfunction "SER_14") (pintype "bidirectional"))
    )
    (net (code "83") (name "Net-(U$3-QH')") (class "Default")
      (node (ref "U$3") (pin "9") (pinfunction "QH'_9") (pintype "bidirectional"))
      (node (ref "U$5") (pin "14") (pinfunction "SER_14") (pintype "bidirectional"))
    )
    (net (code "84") (name "unconnected-(U$2-COM-Pad10)") (class "Default")
      (node (ref "U$2") (pin "10") (pinfunction "COM_10") (pintype "bidirectional"))
    )
    (net (code "85") (name "unconnected-(U$4-COM-Pad10)") (class "Default")
      (node (ref "U$4") (pin "10") (pinfunction "COM_10") (pintype "bidirectional"))
    )
    (net (code "86") (name "unconnected-(U$5-QH'-Pad9)") (class "Default")
      (node (ref "U$5") (pin "9") (pinfunction "QH'_9") (pintype "bidirectional"))
    )
    (net (code "87") (name "unconnected-(U$6-COM-Pad10)") (class "Default")
      (node (ref "U$6") (pin "10") (pinfunction "COM_10") (pintype "bidirectional"))
    )
  )
)
